# Schematic.net
KiCad netlist of a schematic drawn in EAGLE
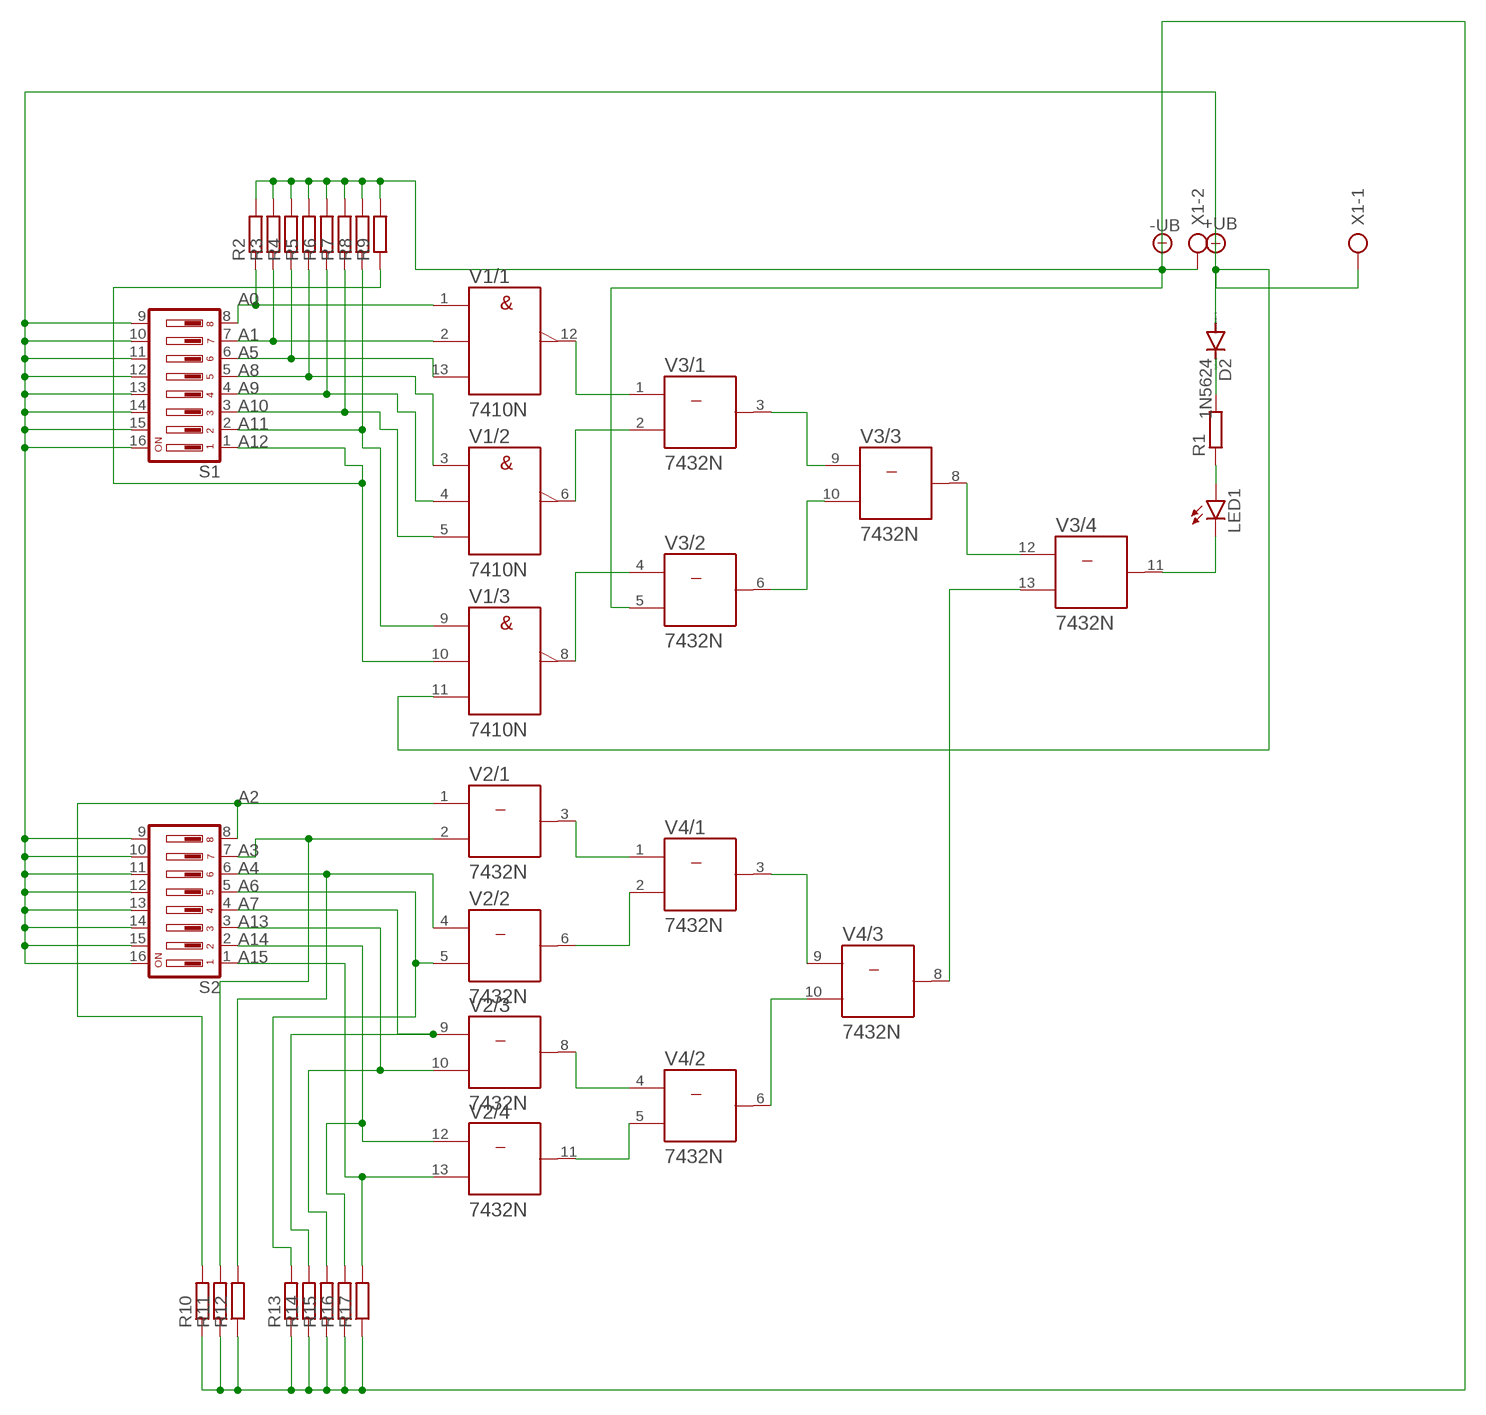
[diagram p0: schematic, sheet 1]

(export (version "E")
  (design (tool "Eeschema 10.0.6"))
  (components
    (comp (ref "D2")
      (value "1N5624")
      (footprint "eagle-import:DO201-15")
      (libsource (lib "eagle-import") (part "1N5624"))
    )
    (comp (ref "LED1")
      (value "LED5MM")
      (footprint "eagle-import:LED5MM")
      (libsource (lib "eagle-import") (part "LED5MM"))
    )
    (comp (ref "R1")
      (value "R-EU_0207/10")
      (footprint "eagle-import:0207_10")
      (libsource (lib "eagle-import") (part "R-EU_0207/10"))
    )
    (comp (ref "R2")
      (value "R-EU_0207/10")
      (footprint "eagle-import:0207_10")
      (libsource (lib "eagle-import") (part "R-EU_0207/10"))
    )
    (comp (ref "R3")
      (value "R-EU_0207/10")
      (footprint "eagle-import:0207_10")
      (libsource (lib "eagle-import") (part "R-EU_0207/10"))
    )
    (comp (ref "R4")
      (value "R-EU_0207/10")
      (footprint "eagle-import:0207_10")
      (libsource (lib "eagle-import") (part "R-EU_0207/10"))
    )
    (comp (ref "R5")
      (value "R-EU_0207/10")
      (footprint "eagle-import:0207_10")
      (libsource (lib "eagle-import") (part "R-EU_0207/10"))
    )
    (comp (ref "R6")
      (value "R-EU_0207/10")
      (footprint "eagle-import:0207_10")
      (libsource (lib "eagle-import") (part "R-EU_0207/10"))
    )
    (comp (ref "R7")
      (value "R-EU_0207/10")
      (footprint "eagle-import:0207_10")
      (libsource (lib "eagle-import") (part "R-EU_0207/10"))
    )
    (comp (ref "R8")
      (value "R-EU_0207/10")
      (footprint "eagle-import:0207_10")
      (libsource (lib "eagle-import") (part "R-EU_0207/10"))
    )
    (comp (ref "R9")
      (value "R-EU_0207/10")
      (footprint "eagle-import:0207_10")
      (libsource (lib "eagle-import") (part "R-EU_0207/10"))
    )
    (comp (ref "R10")
      (value "R-EU_0207/10")
      (footprint "eagle-import:0207_10")
      (libsource (lib "eagle-import") (part "R-EU_0207/10"))
    )
    (comp (ref "R11")
      (value "R-EU_0207/10")
      (footprint "eagle-import:0207_10")
      (libsource (lib "eagle-import") (part "R-EU_0207/10"))
    )
    (comp (ref "R12")
      (value "R-EU_0207/10")
      (footprint "eagle-import:0207_10")
      (libsource (lib "eagle-import") (part "R-EU_0207/10"))
    )
    (comp (ref "R13")
      (value "R-EU_0207/10")
      (footprint "eagle-import:0207_10")
      (libsource (lib "eagle-import") (part "R-EU_0207/10"))
    )
    (comp (ref "R14")
      (value "R-EU_0207/10")
      (footprint "eagle-import:0207_10")
      (libsource (lib "eagle-import") (part "R-EU_0207/10"))
    )
    (comp (ref "R15")
      (value "R-EU_0207/10")
      (footprint "eagle-import:0207_10")
      (libsource (lib "eagle-import") (part "R-EU_0207/10"))
    )
    (comp (ref "R16")
      (value "R-EU_0207/10")
      (footprint "eagle-import:0207_10")
      (libsource (lib "eagle-import") (part "R-EU_0207/10"))
    )
    (comp (ref "R17")
      (value "R-EU_0207/10")
      (footprint "eagle-import:0207_10")
      (libsource (lib "eagle-import") (part "R-EU_0207/10"))
    )
    (comp (ref "S1")
      (value "SD4-08")
      (footprint "eagle-import:SD4-08")
      (libsource (lib "eagle-import") (part "SD4-08"))
    )
    (comp (ref "S2")
      (value "SD4-08")
      (footprint "eagle-import:SD4-08")
      (libsource (lib "eagle-import") (part "SD4-08"))
    )
    (comp (ref "V1")
      (value "7410N")
      (footprint "eagle-import:DIL14")
      (libsource (lib "eagle-import") (part "7410N"))
    )
    (comp (ref "V2")
      (value "7432N")
      (footprint "eagle-import:DIL14")
      (libsource (lib "eagle-import") (part "7432N"))
    )
    (comp (ref "V3")
      (value "7432N")
      (footprint "eagle-import:DIL14")
      (libsource (lib "eagle-import") (part "7432N"))
    )
    (comp (ref "V4")
      (value "7432N")
      (footprint "eagle-import:DIL14")
      (libsource (lib "eagle-import") (part "7432N"))
    )
    (comp (ref "X1")
      (value "AK500/2")
      (footprint "eagle-import:AK500_2")
      (libsource (lib "eagle-import") (part "AK500/2"))
    )
  )
  (nets
    (net (code "1") (name "+UB") (class "Default")
      (node (ref "D2") (pin "A") (pinfunction "A_A") (pintype "passive"))
      (node (ref "S1") (pin "10") (pinfunction "10_10") (pintype "passive"))
      (node (ref "S1") (pin "11") (pinfunction "11_11") (pintype "passive"))
      (node (ref "S1") (pin "12") (pinfunction "12_12") (pintype "passive"))
      (node (ref "S1") (pin "13") (pinfunction "13_13") (pintype "passive"))
      (node (ref "S1") (pin "14") (pinfunction "14_14") (pintype "passive"))
      (node (ref "S1") (pin "15") (pinfunction "15_15") (pintype "passive"))
      (node (ref "S1") (pin "16") (pinfunction "16_16") (pintype "passive"))
      (node (ref "S1") (pin "9") (pinfunction "9_9") (pintype "passive"))
      (node (ref "S2") (pin "10") (pinfunction "10_10") (pintype "passive"))
      (node (ref "S2") (pin "11") (pinfunction "11_11") (pintype "passive"))
      (node (ref "S2") (pin "12") (pinfunction "12_12") (pintype "passive"))
      (node (ref "S2") (pin "13") (pinfunction "13_13") (pintype "passive"))
      (node (ref "S2") (pin "14") (pinfunction "14_14") (pintype "passive"))
      (node (ref "S2") (pin "15") (pinfunction "15_15") (pintype "passive"))
      (node (ref "S2") (pin "16") (pinfunction "16_16") (pintype "passive"))
      (node (ref "S2") (pin "9") (pinfunction "9_9") (pintype "passive"))
      (node (ref "V1") (pin "11") (pinfunction "C_11") (pintype "input"))
      (node (ref "X1") (pin "1") (pinfunction "KL_1") (pintype "passive"))
    )
    (net (code "2") (name "-UB") (class "Default")
      (node (ref "R10") (pin "1") (pinfunction "1_1") (pintype "passive"))
      (node (ref "R11") (pin "1") (pinfunction "1_1") (pintype "passive"))
      (node (ref "R12") (pin "1") (pinfunction "1_1") (pintype "passive"))
      (node (ref "R13") (pin "1") (pinfunction "1_1") (pintype "passive"))
      (node (ref "R14") (pin "1") (pinfunction "1_1") (pintype "passive"))
      (node (ref "R15") (pin "1") (pinfunction "1_1") (pintype "passive"))
      (node (ref "R16") (pin "1") (pinfunction "1_1") (pintype "passive"))
      (node (ref "R17") (pin "1") (pinfunction "1_1") (pintype "passive"))
      (node (ref "R2") (pin "2") (pinfunction "2_2") (pintype "passive"))
      (node (ref "R3") (pin "2") (pinfunction "2_2") (pintype "passive"))
      (node (ref "R4") (pin "2") (pinfunction "2_2") (pintype "passive"))
      (node (ref "R5") (pin "2") (pinfunction "2_2") (pintype "passive"))
      (node (ref "R6") (pin "2") (pinfunction "2_2") (pintype "passive"))
      (node (ref "R7") (pin "2") (pinfunction "2_2") (pintype "passive"))
      (node (ref "R8") (pin "2") (pinfunction "2_2") (pintype "passive"))
      (node (ref "R9") (pin "2") (pinfunction "2_2") (pintype "passive"))
      (node (ref "V3") (pin "5") (pinfunction "B_5") (pintype "input"))
      (node (ref "X1") (pin "2") (pinfunction "KL_2") (pintype "passive"))
    )
    (net (code "3") (name "/A0") (class "Default")
      (node (ref "R2") (pin "1") (pinfunction "1_1") (pintype "passive"))
      (node (ref "S1") (pin "8") (pinfunction "8_8") (pintype "passive"))
      (node (ref "V1") (pin "1") (pinfunction "A_1") (pintype "input"))
    )
    (net (code "4") (name "/A1") (class "Default")
      (node (ref "R3") (pin "1") (pinfunction "1_1") (pintype "passive"))
      (node (ref "S1") (pin "7") (pinfunction "7_7") (pintype "passive"))
      (node (ref "V1") (pin "2") (pinfunction "B_2") (pintype "input"))
    )
    (net (code "5") (name "/A2") (class "Default")
      (node (ref "R10") (pin "2") (pinfunction "2_2") (pintype "passive"))
      (node (ref "S2") (pin "8") (pinfunction "8_8") (pintype "passive"))
      (node (ref "V2") (pin "1") (pinfunction "A_1") (pintype "input"))
    )
    (net (code "6") (name "/A3") (class "Default")
      (node (ref "R11") (pin "2") (pinfunction "2_2") (pintype "passive"))
      (node (ref "S2") (pin "7") (pinfunction "7_7") (pintype "passive"))
      (node (ref "V2") (pin "2") (pinfunction "B_2") (pintype "input"))
    )
    (net (code "7") (name "/A4") (class "Default")
      (node (ref "R12") (pin "2") (pinfunction "2_2") (pintype "passive"))
      (node (ref "S2") (pin "6") (pinfunction "6_6") (pintype "passive"))
      (node (ref "V2") (pin "4") (pinfunction "A_4") (pintype "input"))
    )
    (net (code "8") (name "/A5") (class "Default")
      (node (ref "R4") (pin "1") (pinfunction "1_1") (pintype "passive"))
      (node (ref "S1") (pin "6") (pinfunction "6_6") (pintype "passive"))
      (node (ref "V1") (pin "13") (pinfunction "C_13") (pintype "input"))
    )
    (net (code "9") (name "/A6") (class "Default")
      (node (ref "R13") (pin "2") (pinfunction "2_2") (pintype "passive"))
      (node (ref "S2") (pin "5") (pinfunction "5_5") (pintype "passive"))
      (node (ref "V2") (pin "5") (pinfunction "B_5") (pintype "input"))
    )
    (net (code "10") (name "/A7") (class "Default")
      (node (ref "R14") (pin "2") (pinfunction "2_2") (pintype "passive"))
      (node (ref "S2") (pin "4") (pinfunction "4_4") (pintype "passive"))
      (node (ref "V2") (pin "9") (pinfunction "A_9") (pintype "input"))
    )
    (net (code "11") (name "/A8") (class "Default")
      (node (ref "R5") (pin "1") (pinfunction "1_1") (pintype "passive"))
      (node (ref "S1") (pin "5") (pinfunction "5_5") (pintype "passive"))
      (node (ref "V1") (pin "3") (pinfunction "A_3") (pintype "input"))
    )
    (net (code "12") (name "/A9") (class "Default")
      (node (ref "R6") (pin "1") (pinfunction "1_1") (pintype "passive"))
      (node (ref "S1") (pin "4") (pinfunction "4_4") (pintype "passive"))
      (node (ref "V1") (pin "4") (pinfunction "B_4") (pintype "input"))
    )
    (net (code "13") (name "/A10") (class "Default")
      (node (ref "R7") (pin "1") (pinfunction "1_1") (pintype "passive"))
      (node (ref "S1") (pin "3") (pinfunction "3_3") (pintype "passive"))
      (node (ref "V1") (pin "5") (pinfunction "C_5") (pintype "input"))
    )
    (net (code "14") (name "/A11") (class "Default")
      (node (ref "R8") (pin "1") (pinfunction "1_1") (pintype "passive"))
      (node (ref "S1") (pin "2") (pinfunction "2_2") (pintype "passive"))
      (node (ref "V1") (pin "9") (pinfunction "A_9") (pintype "input"))
    )
    (net (code "15") (name "/A12") (class "Default")
      (node (ref "R9") (pin "1") (pinfunction "1_1") (pintype "passive"))
      (node (ref "S1") (pin "1") (pinfunction "1_1") (pintype "passive"))
      (node (ref "V1") (pin "10") (pinfunction "B_10") (pintype "input"))
    )
    (net (code "16") (name "/A13") (class "Default")
      (node (ref "R15") (pin "2") (pinfunction "2_2") (pintype "passive"))
      (node (ref "S2") (pin "3") (pinfunction "3_3") (pintype "passive"))
      (node (ref "V2") (pin "10") (pinfunction "B_10") (pintype "input"))
    )
    (net (code "17") (name "/A14") (class "Default")
      (node (ref "R16") (pin "2") (pinfunction "2_2") (pintype "passive"))
      (node (ref "S2") (pin "2") (pinfunction "2_2") (pintype "passive"))
      (node (ref "V2") (pin "12") (pinfunction "A_12") (pintype "input"))
    )
    (net (code "18") (name "/A15") (class "Default")
      (node (ref "R17") (pin "2") (pinfunction "2_2") (pintype "passive"))
      (node (ref "S2") (pin "1") (pinfunction "1_1") (pintype "passive"))
      (node (ref "V2") (pin "13") (pinfunction "B_13") (pintype "input"))
    )
    (net (code "19") (name "Net-(D2-PadC)") (class "Default")
      (node (ref "D2") (pin "C") (pinfunction "C_C") (pintype "passive"))
      (node (ref "R1") (pin "2") (pinfunction "2_2") (pintype "passive"))
    )
    (net (code "20") (name "Net-(LED1-C)") (class "Default")
      (node (ref "LED1") (pin "K") (pinfunction "C_K") (pintype "passive"))
      (node (ref "V3") (pin "11") (pinfunction "Y_11") (pintype "output"))
    )
    (net (code "21") (name "Net-(LED1-PadA)") (class "Default")
      (node (ref "LED1") (pin "A") (pinfunction "A_A") (pintype "passive"))
      (node (ref "R1") (pin "1") (pinfunction "1_1") (pintype "passive"))
    )
    (net (code "22") (name "Net-(V1C-Y)") (class "Default")
      (node (ref "V1") (pin "12") (pinfunction "Y_12") (pintype "output"))
      (node (ref "V3") (pin "1") (pinfunction "A_1") (pintype "input"))
    )
    (net (code "23") (name "Net-(V1D-Y)") (class "Default")
      (node (ref "V1") (pin "6") (pinfunction "Y_6") (pintype "output"))
      (node (ref "V3") (pin "2") (pinfunction "B_2") (pintype "input"))
    )
    (net (code "24") (name "Net-(V1E-Y)") (class "Default")
      (node (ref "V1") (pin "8") (pinfunction "Y_8") (pintype "output"))
      (node (ref "V3") (pin "4") (pinfunction "A_4") (pintype "input"))
    )
    (net (code "25") (name "Net-(V2C-Y)") (class "Default")
      (node (ref "V2") (pin "3") (pinfunction "Y_3") (pintype "output"))
      (node (ref "V4") (pin "1") (pinfunction "A_1") (pintype "input"))
    )
    (net (code "26") (name "Net-(V2D-Y)") (class "Default")
      (node (ref "V2") (pin "6") (pinfunction "Y_6") (pintype "output"))
      (node (ref "V4") (pin "2") (pinfunction "B_2") (pintype "input"))
    )
    (net (code "27") (name "Net-(V2E-Y)") (class "Default")
      (node (ref "V2") (pin "8") (pinfunction "Y_8") (pintype "output"))
      (node (ref "V4") (pin "4") (pinfunction "A_4") (pintype "input"))
    )
    (net (code "28") (name "Net-(V2F-Y)") (class "Default")
      (node (ref "V2") (pin "11") (pinfunction "Y_11") (pintype "output"))
      (node (ref "V4") (pin "5") (pinfunction "B_5") (pintype "input"))
    )
    (net (code "29") (name "Net-(V3C-Y)") (class "Default")
      (node (ref "V3") (pin "3") (pinfunction "Y_3") (pintype "output"))
      (node (ref "V3") (pin "9") (pinfunction "A_9") (pintype "input"))
    )
    (net (code "30") (name "Net-(V3D-Y)") (class "Default")
      (node (ref "V3") (pin "10") (pinfunction "B_10") (pintype "input"))
      (node (ref "V3") (pin "6") (pinfunction "Y_6") (pintype "output"))
    )
    (net (code "31") (name "Net-(V3E-Y)") (class "Default")
      (node (ref "V3") (pin "12") (pinfunction "A_12") (pintype "input"))
      (node (ref "V3") (pin "8") (pinfunction "Y_8") (pintype "output"))
    )
    (net (code "32") (name "Net-(V3F-B)") (class "Default")
      (node (ref "V3") (pin "13") (pinfunction "B_13") (pintype "input"))
      (node (ref "V4") (pin "8") (pinfunction "Y_8") (pintype "output"))
    )
    (net (code "33") (name "Net-(V4C-Y)") (class "Default")
      (node (ref "V4") (pin "3") (pinfunction "Y_3") (pintype "output"))
      (node (ref "V4") (pin "9") (pinfunction "A_9") (pintype "input"))
    )
    (net (code "34") (name "Net-(V4D-Y)") (class "Default")
      (node (ref "V4") (pin "10") (pinfunction "B_10") (pintype "input"))
      (node (ref "V4") (pin "6") (pinfunction "Y_6") (pintype "output"))
    )
  )
)
